# Avionics868.net
KiCad netlist of a schematic drawn in EAGLE
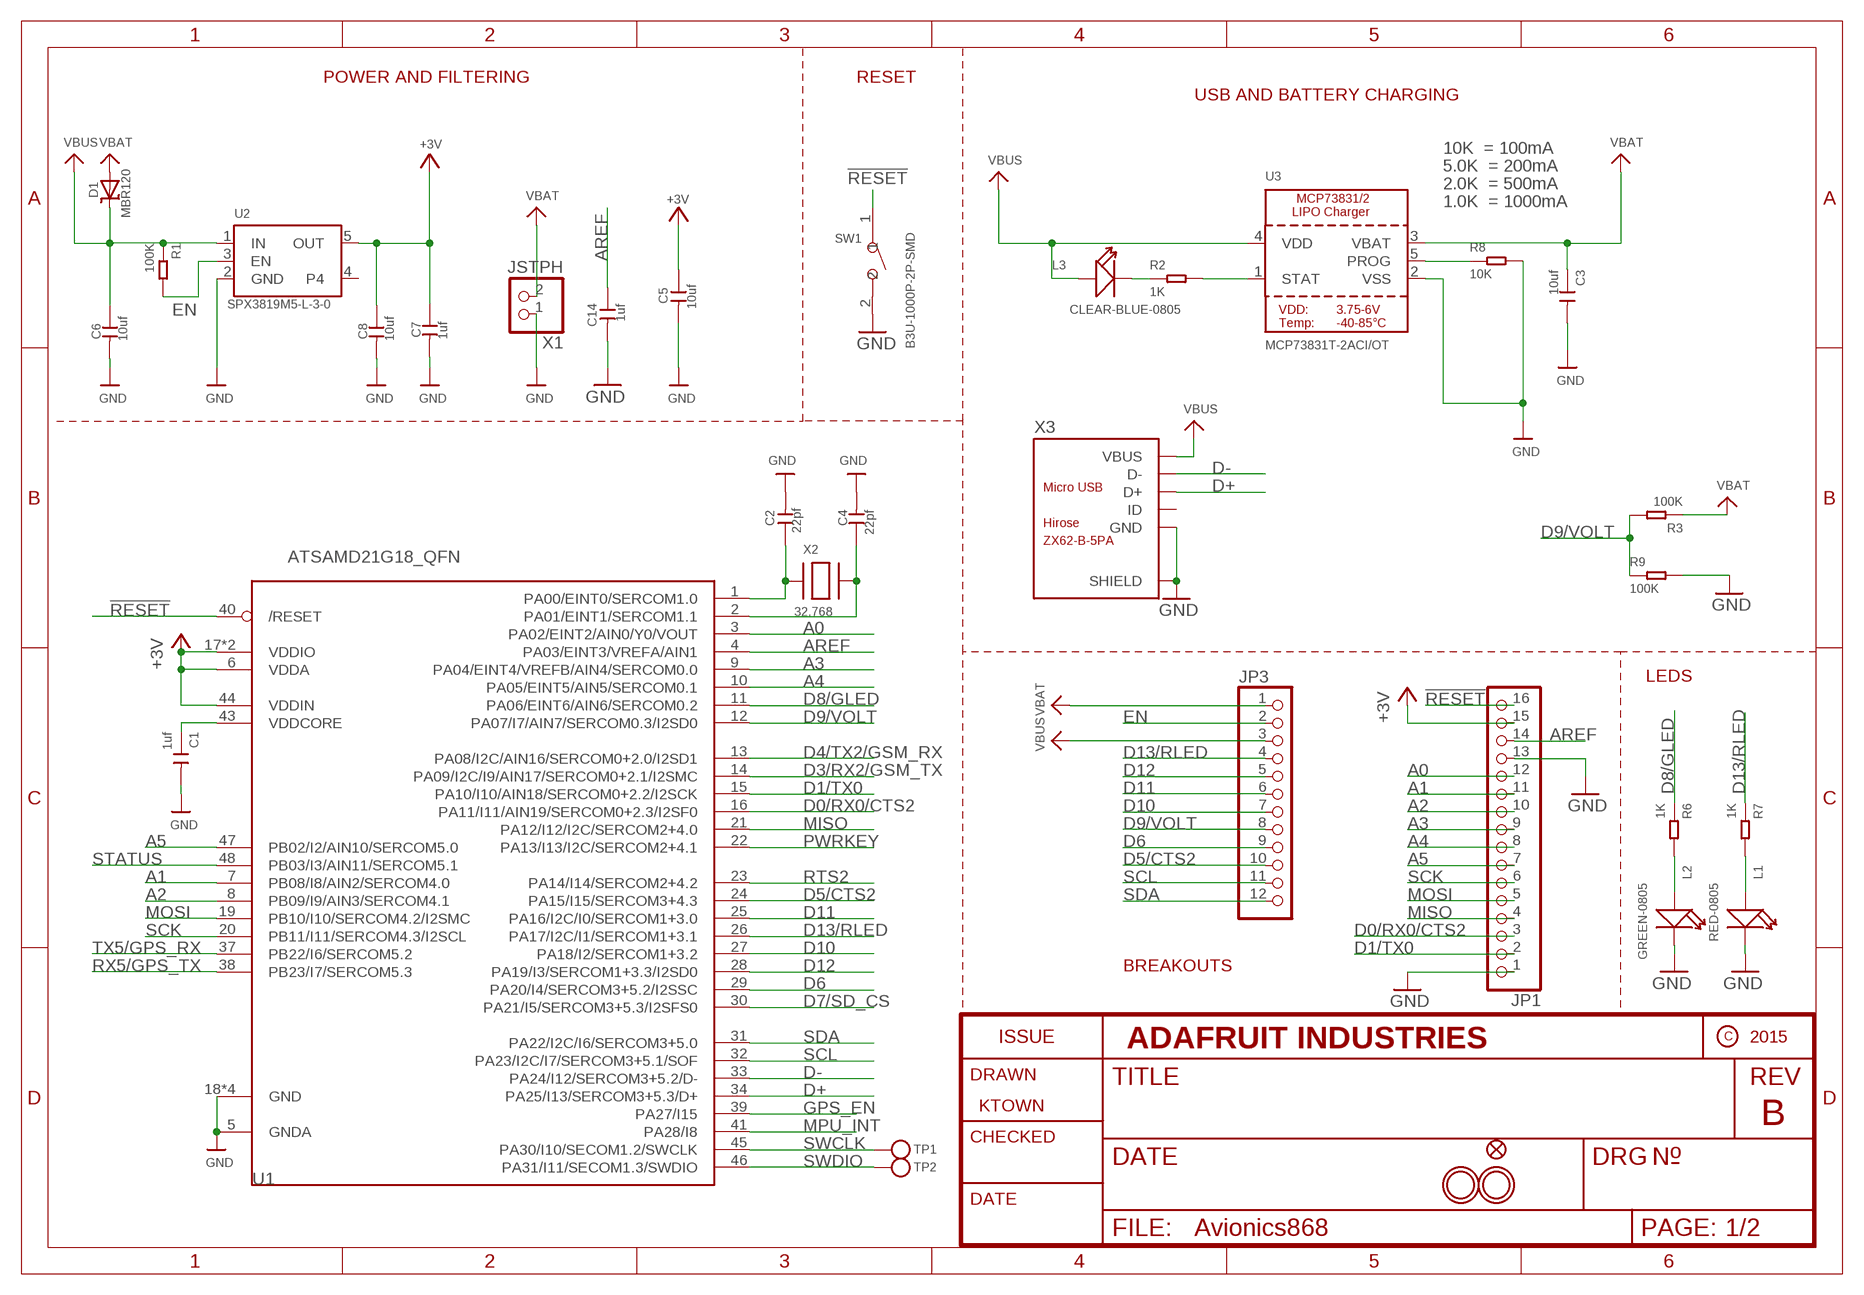
[diagram p0: schematic, sheet 1]
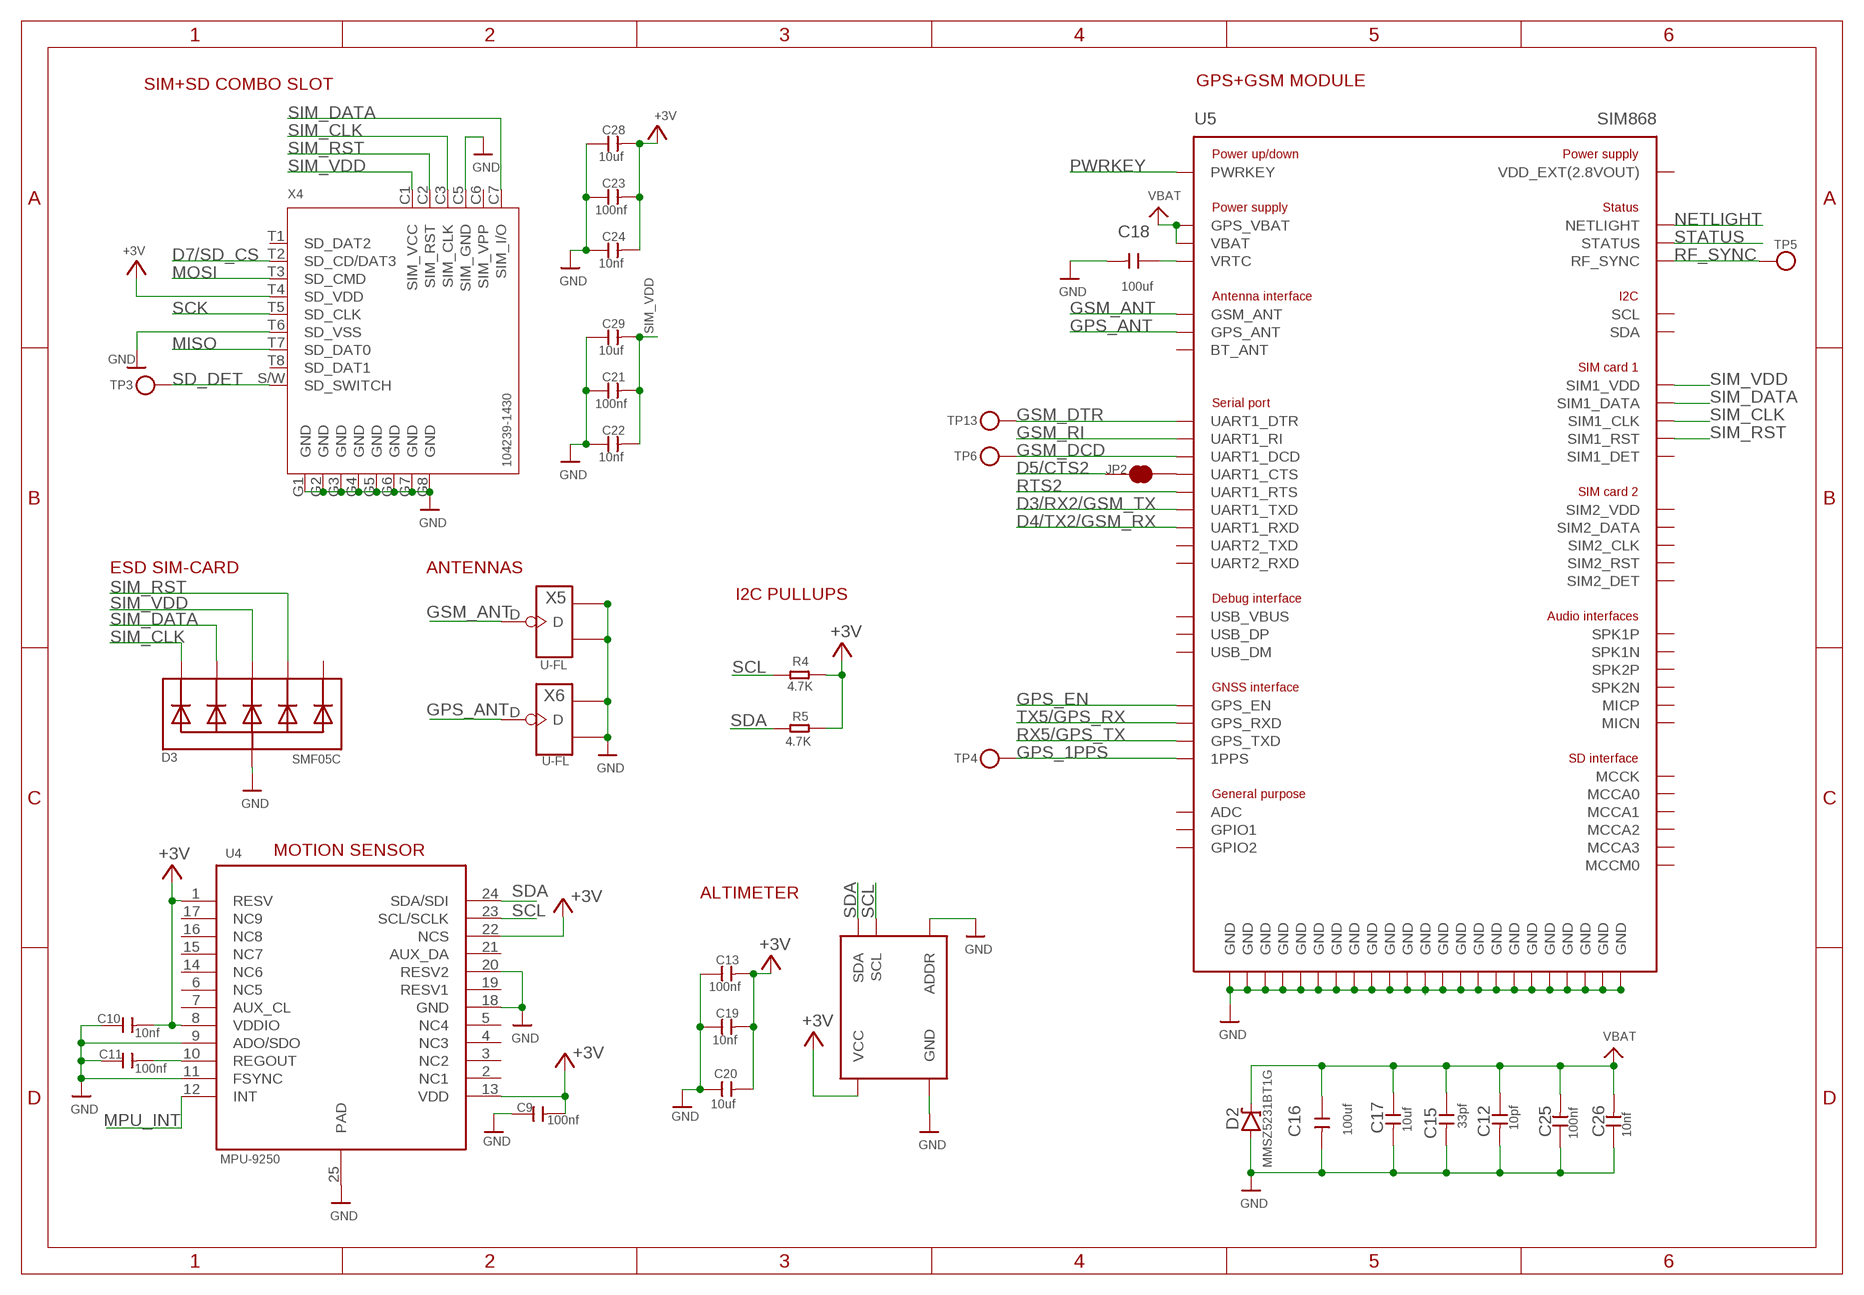
[diagram p1: schematic, sheet 2]

(export (version "E")
  (design (tool "Eeschema 10.0.6"))
  (components
    (comp (ref "C1")
      (value "1uf")
      (footprint "eagle-import:C0603")
      (fields (field (name "MPN") "CC0603KRX7R8BB105"))
      (libsource (lib "eagle-import") (part "CERAMIC-1UF-25V-10%-X7R(0603)"))
    )
    (comp (ref "C2")
      (value "22pf")
      (footprint "eagle-import:C0603")
      (fields (field (name "MPN") "CC0603JRNPO9BN220"))
      (libsource (lib "eagle-import") (part "CERAMIC-22PF-50V-5%-NPO(0603)"))
    )
    (comp (ref "C3")
      (value "10uf")
      (footprint "eagle-import:C0603")
      (fields (field (name "MPN") "CC0603KRX5R6BB106"))
      (libsource (lib "eagle-import") (part "CERAMIC-10UF-10V-10%-X5R(0603)"))
    )
    (comp (ref "C4")
      (value "22pf")
      (footprint "eagle-import:C0603")
      (fields (field (name "MPN") "CC0603JRNPO9BN220"))
      (libsource (lib "eagle-import") (part "CERAMIC-22PF-50V-5%-NPO(0603)"))
    )
    (comp (ref "C5")
      (value "10uf")
      (footprint "eagle-import:C0603")
      (fields (field (name "MPN") "CC0603KRX5R6BB106"))
      (libsource (lib "eagle-import") (part "CERAMIC-10UF-10V-10%-X5R(0603)"))
    )
    (comp (ref "C6")
      (value "10uf")
      (footprint "eagle-import:C0603")
      (fields (field (name "MPN") "CC0603KRX5R6BB106"))
      (libsource (lib "eagle-import") (part "CERAMIC-10UF-10V-10%-X5R(0603)"))
    )
    (comp (ref "C7")
      (value "1uf")
      (footprint "eagle-import:C0603")
      (fields (field (name "MPN") "CC0603KRX7R8BB105"))
      (libsource (lib "eagle-import") (part "CERAMIC-1UF-25V-10%-X7R(0603)"))
    )
    (comp (ref "C8")
      (value "10uf")
      (footprint "eagle-import:C0603")
      (fields (field (name "MPN") "CC0603KRX5R6BB106"))
      (libsource (lib "eagle-import") (part "CERAMIC-10UF-10V-10%-X5R(0603)"))
    )
    (comp (ref "C14")
      (value "1uf")
      (footprint "eagle-import:C0603")
      (fields (field (name "MPN") "CC0603KRX7R8BB105"))
      (libsource (lib "eagle-import") (part "CERAMIC-1UF-25V-10%-X7R(0603)"))
    )
    (comp (ref "D1")
      (value "MBR120")
      (footprint "eagle-import:SOD-123")
      (libsource (lib "eagle-import") (part "DIODE-SCHOTTKYSOD-123"))
    )
    (comp (ref "JP1")
      (value "HEADER-1X16ROUND")
      (footprint "eagle-import:1X16_ROUND")
      (libsource (lib "eagle-import") (part "HEADER-1X16ROUND"))
    )
    (comp (ref "JP3")
      (value "HEADER-1X12")
      (footprint "eagle-import:1X12_ROUND")
      (libsource (lib "eagle-import") (part "HEADER-1X12"))
    )
    (comp (ref "L1")
      (value "RED-0805")
      (footprint "eagle-import:LED-0805")
      (fields (field (name "MPN") "17-215SURC/S530-A2/TR8"))
      (libsource (lib "eagle-import") (part "SMD-LED-CLEAR-RED(0805)"))
    )
    (comp (ref "L2")
      (value "GREEN-0805")
      (footprint "eagle-import:LED-0805")
      (fields (field (name "MPN") "17-215SYGC/S530-E2/TR8"))
      (libsource (lib "eagle-import") (part "SMD-LED-CLEAR-GREEN(0805)"))
    )
    (comp (ref "L3")
      (value "CLEAR-BLUE-0805")
      (footprint "eagle-import:LED-0805")
      (fields (field (name "MPN") "EL-17-215/BHC-AN1P2/3T"))
      (libsource (lib "eagle-import") (part "SMD-LED-CLEAR-BLUE(0805)"))
    )
    (comp (ref "R1")
      (value "100K")
      (footprint "eagle-import:R0603")
      (fields (field (name "MPN") "RC0603JR-07100KL"))
      (libsource (lib "eagle-import") (part "SMD-RES-100K-5%-1/10W(0603)"))
    )
    (comp (ref "R2")
      (value "1K")
      (footprint "eagle-import:R0603")
      (fields (field (name "MPN") "RC0603JR-071KL"))
      (libsource (lib "eagle-import") (part "SMD-RES-1K-5%-1/10W(0603)"))
    )
    (comp (ref "R3")
      (value "100K")
      (footprint "eagle-import:R0603")
      (fields (field (name "MPN") "RC0603FR-07100KL"))
      (libsource (lib "eagle-import") (part "SMD-RES-100K-1%-1/10W(0603)"))
    )
    (comp (ref "R6")
      (value "1K")
      (footprint "eagle-import:R0603")
      (fields (field (name "MPN") "RC0603JR-071KL"))
      (libsource (lib "eagle-import") (part "SMD-RES-1K-5%-1/10W(0603)"))
    )
    (comp (ref "R7")
      (value "1K")
      (footprint "eagle-import:R0603")
      (fields (field (name "MPN") "RC0603JR-071KL"))
      (libsource (lib "eagle-import") (part "SMD-RES-1K-5%-1/10W(0603)"))
    )
    (comp (ref "R8")
      (value "10K")
      (footprint "eagle-import:R0603")
      (fields (field (name "MPN") "RC0603JR-0710KL"))
      (libsource (lib "eagle-import") (part "SMD-RES-10K-5%-1/10W(0603)"))
    )
    (comp (ref "R9")
      (value "100K")
      (footprint "eagle-import:R0603")
      (fields (field (name "MPN") "RC0603FR-07100KL"))
      (libsource (lib "eagle-import") (part "SMD-RES-100K-1%-1/10W(0603)"))
    )
    (comp (ref "SW1")
      (value "B3U-1000P-2P-SMD")
      (footprint "eagle-import:SW2-2.6-3.0X2.5X1.2+0.4MM")
      (libsource (lib "eagle-import") (part "SMD-BUTTON(2P-3.0X2.5X1.2+0.4MM)-B3U-1000P-2P-SMD"))
    )
    (comp (ref "TP1")
      (value "TESTPOINTROUND1.5MM")
      (footprint "eagle-import:TESTPOINT_ROUND_1.5MM")
      (libsource (lib "eagle-import") (part "TESTPOINTROUND1.5MM"))
    )
    (comp (ref "TP2")
      (value "TESTPOINTROUND1.5MM")
      (footprint "eagle-import:TESTPOINT_ROUND_1.5MM")
      (libsource (lib "eagle-import") (part "TESTPOINTROUND1.5MM"))
    )
    (comp (ref "U$31")
      (value "MOUNTINGHOLE2.5")
      (footprint "eagle-import:MOUNTINGHOLE_2.5_PLATED")
      (libsource (lib "eagle-import") (part "MOUNTINGHOLE2.5"))
    )
    (comp (ref "U$32")
      (value "MOUNTINGHOLE2.5")
      (footprint "eagle-import:MOUNTINGHOLE_2.5_PLATED")
      (libsource (lib "eagle-import") (part "MOUNTINGHOLE2.5"))
    )
    (comp (ref "U$34")
      (value "FIDUCIAL\"\"")
      (footprint "eagle-import:FIDUCIAL_1MM")
      (libsource (lib "eagle-import") (part "FIDUCIAL{dblquote}{dblquote}"))
    )
    (comp (ref "U1")
      (value "ATSAMD21G18_QFN")
      (footprint "eagle-import:TQFN48_7MM")
      (libsource (lib "eagle-import") (part "ATSAMD21J_QFN"))
    )
    (comp (ref "U2")
      (value "SPX3819M5-L-3-0")
      (footprint "eagle-import:SOT23-5")
      (libsource (lib "eagle-import") (part "VREG_SOT23-5"))
    )
    (comp (ref "U3")
      (value "MCP73831T-2ACI/OT")
      (footprint "eagle-import:SOT23-5")
      (libsource (lib "eagle-import") (part "MCP73831/2"))
    )
    (comp (ref "X1")
      (value "JSTPH")
      (footprint "eagle-import:JSTPH2")
      (libsource (lib "eagle-import") (part "CON_JST_PH_2PIN"))
    )
    (comp (ref "X2")
      (value "32.768")
      (footprint "eagle-import:XTAL3215")
      (libsource (lib "eagle-import") (part "XTAL-3.2X1.5"))
    )
    (comp (ref "X3")
      (value "ZX62-B-5PA")
      (footprint "eagle-import:MICRO-USB5+6P-SMD-0.65-AB")
      (fields (field (name "MFR") "Generic") (field (name "MPN") "AO1SB141B1-067"))
      (libsource (lib "eagle-import") (part "AO1SB141B1-067"))
    )
    (comp (ref "C9")
      (value "100nf")
      (footprint "eagle-import:C0603")
      (fields (field (name "MPN") "CC0603KRX7R9BB104"))
      (libsource (lib "eagle-import") (part "CERAMIC-100NF-50V-10%-X7R(0603)"))
    )
    (comp (ref "C10")
      (value "10nf")
      (footprint "eagle-import:C0603")
      (fields (field (name "MPN") "CC0603KRX7R9BB103"))
      (libsource (lib "eagle-import") (part "CERAMIC-10NF-50V-10%-X7R(0603)"))
    )
    (comp (ref "C11")
      (value "100nf")
      (footprint "eagle-import:C0603")
      (fields (field (name "MPN") "CC0603KRX7R9BB104"))
      (libsource (lib "eagle-import") (part "CERAMIC-100NF-50V-10%-X7R(0603)"))
    )
    (comp (ref "C12")
      (value "10pf")
      (footprint "eagle-import:C0603")
      (fields (field (name "MPN") "CC0603JRNPO9BN100"))
      (libsource (lib "eagle-import") (part "CERAMIC-10PF-50V-5%-NPO(0603)"))
    )
    (comp (ref "C13")
      (value "100nf")
      (footprint "eagle-import:C0603")
      (fields (field (name "MPN") "CC0603KRX7R9BB104"))
      (libsource (lib "eagle-import") (part "CERAMIC-100NF-50V-10%-X7R(0603)"))
    )
    (comp (ref "C15")
      (value "33pf")
      (footprint "eagle-import:C0603")
      (fields (field (name "MPN") "CC0603JRNPO9BN330"))
      (libsource (lib "eagle-import") (part "CERAMIC-33PF-50V-5%-NPO(0603)"))
    )
    (comp (ref "C16")
      (value "100uf")
      (footprint "eagle-import:C1206")
      (fields (field (name "MPN") "GRM31CR60J107ME39L"))
      (libsource (lib "eagle-import") (part "CERAMIC-100UF-6.3V-20%-X5R(1206)"))
    )
    (comp (ref "C17")
      (value "10uf")
      (footprint "eagle-import:C0603")
      (fields (field (name "MPN") "CC0603KRX5R6BB106"))
      (libsource (lib "eagle-import") (part "CERAMIC-10UF-10V-10%-X5R(0603)"))
    )
    (comp (ref "C18")
      (value "100uf")
      (footprint "eagle-import:C1206")
      (fields (field (name "MPN") "GRM31CR60J107ME39L"))
      (libsource (lib "eagle-import") (part "CERAMIC-100UF-6.3V-20%-X5R(1206)"))
    )
    (comp (ref "C19")
      (value "10nf")
      (footprint "eagle-import:C0603")
      (fields (field (name "MPN") "CC0603KRX7R9BB103"))
      (libsource (lib "eagle-import") (part "CERAMIC-10NF-50V-10%-X7R(0603)"))
    )
    (comp (ref "C20")
      (value "10uf")
      (footprint "eagle-import:C0603")
      (fields (field (name "MPN") "CC0603KRX5R6BB106"))
      (libsource (lib "eagle-import") (part "CERAMIC-10UF-10V-10%-X5R(0603)"))
    )
    (comp (ref "C21")
      (value "100nf")
      (footprint "eagle-import:C0603")
      (fields (field (name "MPN") "CC0603KRX7R9BB104"))
      (libsource (lib "eagle-import") (part "CERAMIC-100NF-50V-10%-X7R(0603)"))
    )
    (comp (ref "C22")
      (value "10nf")
      (footprint "eagle-import:C0603")
      (fields (field (name "MPN") "CC0603KRX7R9BB103"))
      (libsource (lib "eagle-import") (part "CERAMIC-10NF-50V-10%-X7R(0603)"))
    )
    (comp (ref "C23")
      (value "100nf")
      (footprint "eagle-import:C0603")
      (fields (field (name "MPN") "CC0603KRX7R9BB104"))
      (libsource (lib "eagle-import") (part "CERAMIC-100NF-50V-10%-X7R(0603)"))
    )
    (comp (ref "C24")
      (value "10nf")
      (footprint "eagle-import:C0603")
      (fields (field (name "MPN") "CC0603KRX7R9BB103"))
      (libsource (lib "eagle-import") (part "CERAMIC-10NF-50V-10%-X7R(0603)"))
    )
    (comp (ref "C25")
      (value "100nf")
      (footprint "eagle-import:C0603")
      (fields (field (name "MPN") "CC0603KRX7R9BB104"))
      (libsource (lib "eagle-import") (part "CERAMIC-100NF-50V-10%-X7R(0603)"))
    )
    (comp (ref "C26")
      (value "10nf")
      (footprint "eagle-import:C0603")
      (fields (field (name "MPN") "CC0603KRX7R9BB103"))
      (libsource (lib "eagle-import") (part "CERAMIC-10NF-50V-10%-X7R(0603)"))
    )
    (comp (ref "C28")
      (value "10uf")
      (footprint "eagle-import:C0603")
      (fields (field (name "MPN") "CC0603KRX5R6BB106"))
      (libsource (lib "eagle-import") (part "CERAMIC-10UF-10V-10%-X5R(0603)"))
    )
    (comp (ref "C29")
      (value "10uf")
      (footprint "eagle-import:C0603")
      (fields (field (name "MPN") "CC0603KRX5R6BB106"))
      (libsource (lib "eagle-import") (part "CERAMIC-10UF-10V-10%-X5R(0603)"))
    )
    (comp (ref "D2")
      (value "MMSZ5231BT1G")
      (footprint "eagle-import:SOD-123")
      (fields (field (name "MFR") "ON SEMICONDUCTOR"))
      (libsource (lib "eagle-import") (part "MMSZ5231BT1G"))
    )
    (comp (ref "D3")
      (value "SMF05C")
      (footprint "eagle-import:SOT363")
      (libsource (lib "eagle-import") (part "TVSARRAY_5LANE"))
    )
    (comp (ref "JP2")
      (value "JUMPER-PAD-2-NC_BY_TRACE")
      (footprint "eagle-import:PAD-JUMPER-2-NC_BY_TRACE_YES_SILK")
      (libsource (lib "eagle-import") (part "JUMPER-PAD-2-NC_BY_TRACE"))
    )
    (comp (ref "R4")
      (value "4.7K")
      (footprint "eagle-import:R0603")
      (fields (field (name "MPN") "RC0603JR-074K7L"))
      (libsource (lib "eagle-import") (part "SMD-RES-4.7K-5%-1/10W(0603)"))
    )
    (comp (ref "R5")
      (value "4.7K")
      (footprint "eagle-import:R0603")
      (fields (field (name "MPN") "RC0603JR-074K7L"))
      (libsource (lib "eagle-import") (part "SMD-RES-4.7K-5%-1/10W(0603)"))
    )
    (comp (ref "TP3")
      (value "TESTPOINTROUND1.5MM")
      (footprint "eagle-import:TESTPOINT_ROUND_1.5MM")
      (libsource (lib "eagle-import") (part "TESTPOINTROUND1.5MM"))
    )
    (comp (ref "TP4")
      (value "TESTPOINTROUND1.5MM")
      (footprint "eagle-import:TESTPOINT_ROUND_1.5MM")
      (libsource (lib "eagle-import") (part "TESTPOINTROUND1.5MM"))
    )
    (comp (ref "TP5")
      (value "TESTPOINTROUND1.5MM")
      (footprint "eagle-import:TESTPOINT_ROUND_1.5MM")
      (libsource (lib "eagle-import") (part "TESTPOINTROUND1.5MM"))
    )
    (comp (ref "TP6")
      (value "TESTPOINTROUND1.5MM")
      (footprint "eagle-import:TESTPOINT_ROUND_1.5MM")
      (libsource (lib "eagle-import") (part "TESTPOINTROUND1.5MM"))
    )
    (comp (ref "TP13")
      (value "TESTPOINTROUND1.5MM")
      (footprint "eagle-import:TESTPOINT_ROUND_1.5MM")
      (libsource (lib "eagle-import") (part "TESTPOINTROUND1.5MM"))
    )
    (comp (ref "U4")
      (value "MPU-9250")
      (footprint "eagle-import:LEAD-QFN24")
      (libsource (lib "eagle-import") (part "MPU-9250"))
    )
    (comp (ref "U5")
      (value "SIM868")
      (footprint "eagle-import:SIM868")
      (libsource (lib "eagle-import") (part "SIM868"))
    )
    (comp (ref "U6")
      (value "BMP280")
      (footprint "eagle-import:LGA-8")
      (libsource (lib "eagle-import") (part "BMP280"))
    )
    (comp (ref "X4")
      (value "104239-1430")
      (footprint "eagle-import:MOLEX-SD+SIM-104239")
      (fields (field (name "MPN") "VSHO-21-3301"))
      (libsource (lib "eagle-import") (part "MOLEX-SD+SIM-104239"))
    )
    (comp (ref "X5")
      (value "U-FL")
      (footprint "eagle-import:U-FL3P-SMD-2.6X2.6X1.0MM")
      (libsource (lib "eagle-import") (part "ANTENNA-CONN-U-FL(3P)"))
    )
    (comp (ref "X6")
      (value "U-FL")
      (footprint "eagle-import:U-FL3P-SMD-2.6X2.6X1.0MM")
      (libsource (lib "eagle-import") (part "ANTENNA-CONN-U-FL(3P)"))
    )
  )
  (nets
    (net (code "1") (name "+3V") (class "Default")
      (node (ref "C10") (pin "2") (pinfunction "2_2") (pintype "passive"))
      (node (ref "C13") (pin "2") (pinfunction "2_2") (pintype "passive"))
      (node (ref "C19") (pin "2") (pinfunction "2_2") (pintype "passive"))
      (node (ref "C20") (pin "2") (pinfunction "2_2") (pintype "passive"))
      (node (ref "C23") (pin "2") (pinfunction "2_2") (pintype "passive"))
      (node (ref "C24") (pin "2") (pinfunction "2_2") (pintype "passive"))
      (node (ref "C28") (pin "2") (pinfunction "2_2") (pintype "passive"))
      (node (ref "C5") (pin "1") (pinfunction "1_1") (pintype "passive"))
      (node (ref "C7") (pin "1") (pinfunction "1_1") (pintype "passive"))
      (node (ref "C8") (pin "1") (pinfunction "1_1") (pintype "passive"))
      (node (ref "C9") (pin "2") (pinfunction "2_2") (pintype "passive"))
      (node (ref "JP1") (pin "15") (pinfunction "15_15") (pintype "passive"))
      (node (ref "R4") (pin "2") (pinfunction "2_2") (pintype "passive"))
      (node (ref "R5") (pin "2") (pinfunction "2_2") (pintype "passive"))
      (node (ref "U1") (pin "17") (pinfunction "VDDIO_17") (pintype "power_in"))
      (node (ref "U1") (pin "36") (pinfunction "VDDIO_36") (pintype "power_in"))
      (node (ref "U1") (pin "44") (pinfunction "VDDIN_44") (pintype "power_in"))
      (node (ref "U1") (pin "6") (pinfunction "VDDA_6") (pintype "power_in"))
      (node (ref "U2") (pin "5") (pinfunction "OUT_5") (pintype "power_in"))
      (node (ref "U4") (pin "1") (pinfunction "RESV_1") (pintype "bidirectional"))
      (node (ref "U4") (pin "13") (pinfunction "VDD_13") (pintype "bidirectional"))
      (node (ref "U4") (pin "22") (pinfunction "NCS_22") (pintype "bidirectional"))
      (node (ref "U4") (pin "8") (pinfunction "VDDIO_8") (pintype "bidirectional"))
      (node (ref "U6") (pin "P2") (pinfunction "VCC_P2") (pintype "bidirectional"))
      (node (ref "U6") (pin "P6") (pinfunction "VCC_P6") (pintype "bidirectional"))
      (node (ref "U6") (pin "P8") (pinfunction "VCC_P8") (pintype "bidirectional"))
      (node (ref "X4") (pin "T4") (pinfunction "SD_VDD_T4") (pintype "bidirectional"))
    )
    (net (code "2") (name "A0") (class "Default")
      (node (ref "JP1") (pin "12") (pinfunction "12_12") (pintype "passive"))
      (node (ref "U1") (pin "3") (pinfunction "PA02/EINT2/AIN0/Y0/VOUT_3") (pintype "bidirectional"))
    )
    (net (code "3") (name "A1") (class "Default")
      (node (ref "JP1") (pin "11") (pinfunction "11_11") (pintype "passive"))
      (node (ref "U1") (pin "7") (pinfunction "PB08/I8/AIN2/SERCOM4.0_7") (pintype "bidirectional"))
    )
    (net (code "4") (name "A2") (class "Default")
      (node (ref "JP1") (pin "10") (pinfunction "10_10") (pintype "passive"))
      (node (ref "U1") (pin "8") (pinfunction "PB09/I9/AIN3/SERCOM4.1_8") (pintype "bidirectional"))
    )
    (net (code "5") (name "A3") (class "Default")
      (node (ref "JP1") (pin "9") (pinfunction "9_9") (pintype "passive"))
      (node (ref "U1") (pin "9") (pinfunction "PA04/EINT4/VREFB/AIN4/SERCOM0.0_9") (pintype "bidirectional"))
    )
    (net (code "6") (name "A4") (class "Default")
      (node (ref "JP1") (pin "8") (pinfunction "8_8") (pintype "passive"))
      (node (ref "U1") (pin "10") (pinfunction "PA05/EINT5/AIN5/SERCOM0.1_10") (pintype "bidirectional"))
    )
    (net (code "7") (name "A5") (class "Default")
      (node (ref "JP1") (pin "7") (pinfunction "7_7") (pintype "passive"))
      (node (ref "U1") (pin "47") (pinfunction "PB02/I2/AIN10/SERCOM5.0_47") (pintype "bidirectional"))
    )
    (net (code "8") (name "AREF") (class "Default")
      (node (ref "C14") (pin "1") (pinfunction "1_1") (pintype "passive"))
      (node (ref "JP1") (pin "14") (pinfunction "14_14") (pintype "passive"))
      (node (ref "U1") (pin "4") (pinfunction "PA03/EINT3/VREFA/AIN1_4") (pintype "bidirectional"))
    )
    (net (code "9") (name "D+") (class "Default")
      (node (ref "U1") (pin "34") (pinfunction "PA25/I13/SERCOM3+5.3/D+_34") (pintype "bidirectional"))
      (node (ref "X3") (pin "3") (pinfunction "D+_3") (pintype "bidirectional"))
    )
    (net (code "10") (name "D-") (class "Default")
      (node (ref "U1") (pin "33") (pinfunction "PA24/I12/SERCOM3+5.2/D-_33") (pintype "bidirectional"))
      (node (ref "X3") (pin "2") (pinfunction "D-_2") (pintype "bidirectional"))
    )
    (net (code "11") (name "D0{slash}RX0{slash}CTS2") (class "Default")
      (node (ref "JP1") (pin "3") (pinfunction "3_3") (pintype "passive"))
      (node (ref "U1") (pin "16") (pinfunction "PA11/I11/AIN19/SERCOM0+2.3/I2SF0_16") (pintype "bidirectional"))
    )
    (net (code "12") (name "D1{slash}TX0") (class "Default")
      (node (ref "JP1") (pin "2") (pinfunction "2_2") (pintype "passive"))
      (node (ref "U1") (pin "15") (pinfunction "PA10/I10/AIN18/SERCOM0+2.2/I2SCK_15") (pintype "bidirectional"))
    )
    (net (code "13") (name "D3{slash}RX2{slash}GSM_TX") (class "Default")
      (node (ref "U1") (pin "14") (pinfunction "PA09/I2C/I9/AIN17/SERCOM0+2.1/I2SMC_14") (pintype "bidirectional"))
      (node (ref "U5") (pin "1_") (pinfunction "UART1_TXD_1_") (pintype "output"))
    )
    (net (code "14") (name "D4{slash}TX2{slash}GSM_RX") (class "Default")
      (node (ref "U1") (pin "13") (pinfunction "PA08/I2C/AIN16/SERCOM0+2.0/I2SD1_13") (pintype "bidirectional"))
      (node (ref "U5") (pin "2_") (pinfunction "UART1_RXD_2_") (pintype "input"))
    )
    (net (code "15") (name "D5{slash}CTS2") (class "Default")
      (node (ref "JP2") (pin "1") (pinfunction "1_1") (pintype "passive"))
      (node (ref "JP3") (pin "10") (pinfunction "10_10") (pintype "passive"))
      (node (ref "U1") (pin "24") (pinfunction "PA15/I15/SERCOM3+4.3_24") (pintype "bidirectional"))
    )
    (net (code "16") (name "D6") (class "Default")
      (node (ref "JP3") (pin "9") (pinfunction "9_9") (pintype "passive"))
      (node (ref "U1") (pin "29") (pinfunction "PA20/I4/SERCOM3+5.2/I2SSC_29") (pintype "bidirectional"))
    )
    (net (code "17") (name "D7{slash}SD_CS") (class "Default")
      (node (ref "U1") (pin "30") (pinfunction "PA21/I5/SERCOM3+5.3/I2SFS0_30") (pintype "bidirectional"))
      (node (ref "X4") (pin "T2") (pinfunction "SD_CD/DAT3_T2") (pintype "bidirectional"))
    )
    (net (code "18") (name "D8{slash}GLED") (class "Default")
      (node (ref "R6") (pin "1") (pinfunction "1_1") (pintype "passive"))
      (node (ref "U1") (pin "11") (pinfunction "PA06/EINT6/AIN6/SERCOM0.2_11") (pintype "bidirectional"))
    )
    (net (code "19") (name "D9{slash}VOLT") (class "Default")
      (node (ref "JP3") (pin "8") (pinfunction "8_8") (pintype "passive"))
      (node (ref "R3") (pin "2") (pinfunction "2_2") (pintype "passive"))
      (node (ref "R9") (pin "1") (pinfunction "1_1") (pintype "passive"))
      (node (ref "U1") (pin "12") (pinfunction "PA07/I7/AIN7/SERCOM0.3/I2SD0_12") (pintype "bidirectional"))
    )
    (net (code "20") (name "D10") (class "Default")
      (node (ref "JP3") (pin "7") (pinfunction "7_7") (pintype "passive"))
      (node (ref "U1") (pin "27") (pinfunction "PA18/I2/SERCOM1+3.2_27") (pintype "bidirectional"))
    )
    (net (code "21") (name "D11") (class "Default")
      (node (ref "JP3") (pin "6") (pinfunction "6_6") (pintype "passive"))
      (node (ref "U1") (pin "25") (pinfunction "PA16/I2C/I0/SERCOM1+3.0_25") (pintype "bidirectional"))
    )
    (net (code "22") (name "D12") (class "Default")
      (node (ref "JP3") (pin "5") (pinfunction "5_5") (pintype "passive"))
      (node (ref "U1") (pin "28") (pinfunction "PA19/I3/SERCOM1+3.3/I2SD0_28") (pintype "bidirectional"))
    )
    (net (code "23") (name "D13{slash}RLED") (class "Default")
      (node (ref "JP3") (pin "4") (pinfunction "4_4") (pintype "passive"))
      (node (ref "R7") (pin "1") (pinfunction "1_1") (pintype "passive"))
      (node (ref "U1") (pin "26") (pinfunction "PA17/I2C/I1/SERCOM1+3.1_26") (pintype "bidirectional"))
    )
    (net (code "24") (name "EN") (class "Default")
      (node (ref "JP3") (pin "2") (pinfunction "2_2") (pintype "passive"))
      (node (ref "R1") (pin "2") (pinfunction "2_2") (pintype "passive"))
      (node (ref "U2") (pin "3") (pinfunction "EN_3") (pintype "input"))
    )
    (net (code "25") (name "GND") (class "Default")
      (node (ref "C1") (pin "2") (pinfunction "2_2") (pintype "passive"))
      (node (ref "C10") (pin "1") (pinfunction "1_1") (pintype "passive"))
      (node (ref "C11") (pin "1") (pinfunction "1_1") (pintype "passive"))
      (node (ref "C12") (pin "2") (pinfunction "2_2") (pintype "passive"))
      (node (ref "C13") (pin "1") (pinfunction "1_1") (pintype "passive"))
      (node (ref "C14") (pin "2") (pinfunction "2_2") (pintype "passive"))
      (node (ref "C15") (pin "2") (pinfunction "2_2") (pintype "passive"))
      (node (ref "C16") (pin "2") (pinfunction "2_2") (pintype "passive"))
      (node (ref "C17") (pin "2") (pinfunction "2_2") (pintype "passive"))
      (node (ref "C18") (pin "2") (pinfunction "2_2") (pintype "passive"))
      (node (ref "C19") (pin "1") (pinfunction "1_1") (pintype "passive"))
      (node (ref "C2") (pin "2") (pinfunction "2_2") (pintype "passive"))
      (node (ref "C20") (pin "1") (pinfunction "1_1") (pintype "passive"))
      (node (ref "C21") (pin "1") (pinfunction "1_1") (pintype "passive"))
      (node (ref "C22") (pin "1") (pinfunction "1_1") (pintype "passive"))
      (node (ref "C23") (pin "1") (pinfunction "1_1") (pintype "passive"))
      (node (ref "C24") (pin "1") (pinfunction "1_1") (pintype "passive"))
      (node (ref "C25") (pin "1") (pinfunction "1_1") (pintype "passive"))
      (node (ref "C26") (pin "1") (pinfunction "1_1") (pintype "passive"))
      (node (ref "C28") (pin "1") (pinfunction "1_1") (pintype "passive"))
      (node (ref "C29") (pin "1") (pinfunction "1_1") (pintype "passive"))
      (node (ref "C3") (pin "2") (pinfunction "2_2") (pintype "passive"))
      (node (ref "C4") (pin "2") (pinfunction "2_2") (pintype "passive"))
      (node (ref "C5") (pin "2") (pinfunction "2_2") (pintype "passive"))
      (node (ref "C6") (pin "2") (pinfunction "2_2") (pintype "passive"))
      (node (ref "C7") (pin "2") (pinfunction "2_2") (pintype "passive"))
      (node (ref "C8") (pin "2") (pinfunction "2_2") (pintype "passive"))
      (node (ref "C9") (pin "1") (pinfunction "1_1") (pintype "passive"))
      (node (ref "D2") (pin "A") (pinfunction "A_A") (pintype "passive"))
      (node (ref "D3") (pin "2") (pinfunction "A_2") (pintype "passive"))
      (node (ref "JP1") (pin "1") (pinfunction "1_1") (pintype "passive"))
      (node (ref "JP1") (pin "13") (pinfunction "13_13") (pintype "passive"))
      (node (ref "L1") (pin "-") (pinfunction "-_-") (pintype "passive"))
      (node (ref "L2") (pin "-") (pinfunction "-_-") (pintype "passive"))
      (node (ref "R8") (pin "2") (pinfunction "2_2") (pintype "passive"))
      (node (ref "R9") (pin "2") (pinfunction "2_2") (pintype "passive"))
      (node (ref "SW1") (pin "2") (pinfunction "2_2") (pintype "bidirectional"))
      (node (ref "U1") (pin "18") (pinfunction "GND_18") (pintype "power_in"))
      (node (ref "U1") (pin "35") (pinfunction "GND_35") (pintype "power_in"))
      (node (ref "U1") (pin "42") (pinfunction "GND_42") (pintype "power_in"))
      (node (ref "U1") (pin "5") (pinfunction "GNDA_5") (pintype "power_in"))
      (node (ref "U1") (pin "THERMAL") (pinfunction "GND_THERMAL") (pintype "power_in"))
      (node (ref "U2") (pin "2") (pinfunction "GND_2") (pintype "power_in"))
      (node (ref "U3") (pin "2") (pinfunction "VSS_2") (pintype "power_in"))
      (node (ref "U4") (pin "11") (pinfunction "FSYNC_11") (pintype "bidirectional"))
      (node (ref "U4") (pin "18") (pinfunction "GND_18") (pintype "bidirectional"))
      (node (ref "U4") (pin "20") (pinfunction "RESV2_20") (pintype "bidirectional"))
      (node (ref "U4") (pin "25") (pinfunction "PAD_25") (pintype "bidirectional"))
      (node (ref "U4") (pin "9") (pinfunction "ADO/SDO_9") (pintype "bidirectional"))
      (node (ref "U5") (pin "13_") (pinfunction "GND_13_") (pintype "power_in"))
      (node (ref "U5") (pin "19_") (pinfunction "GND_19_") (pintype "power_in"))
      (node (ref "U5") (pin "21_") (pinfunction "GND_21_") (pintype "power_in"))
      (node (ref "U5") (pin "27_") (pinfunction "GND_27_") (pintype "power_in"))
      (node (ref "U5") (pin "30_") (pinfunction "GND_30_") (pintype "power_in"))
      (node (ref "U5") (pin "31_") (pinfunction "GND_31_") (pintype "power_in"))
      (node (ref "U5") (pin "33_") (pinfunction "GND_33_") (pintype "power_in"))
      (node (ref "U5") (pin "36_") (pinfunction "GND_36_") (pintype "power_in"))
      (node (ref "U5") (pin "37_") (pinfunction "GND_37_") (pintype "power_in"))
      (node (ref "U5") (pin "45_") (pinfunction "GND_45_") (pintype "power_in"))
      (node (ref "U5") (pin "63_") (pinfunction "GND_63_") (pintype "power_in"))
      (node (ref "U5") (pin "66_") (pinfunction "GND_66_") (pintype "power_in"))
      (node (ref "U5") (pin "67_") (pinfunction "GND_67_") (pintype "power_in"))
      (node (ref "U5") (pin "69_") (pinfunction "GND_69_") (pintype "power_in"))
      (node (ref "U5") (pin "70_") (pinfunction "GND_70_") (pintype "power_in"))
      (node (ref "U5") (pin "71_") (pinfunction "GND_71_") (pintype "power_in"))
      (node (ref "U5") (pin "72_") (pinfunction "GND_72_") (pintype "power_in"))
      (node (ref "U5") (pin "73_") (pinfunction "GND_73_") (pintype "power_in"))
      (node (ref "U5") (pin "74_") (pinfunction "GND_74_") (pintype "power_in"))
      (node (ref "U5") (pin "75_") (pinfunction "GND_75_") (pintype "power_in"))
      (node (ref "U5") (pin "76_") (pinfunction "GND_76_") (pintype "power_in"))
      (node (ref "U5") (pin "77_") (pinfunction "GND_77_") (pintype "power_in"))
      (node (ref "U5") (pin "8_") (pinfunction "GND_8_") (pintype "power_in"))
      (node (ref "U6") (pin "P1") (pinfunction "GND_P1") (pintype "bidirectional"))
      (node (ref "U6") (pin "P5") (pinfunction "ADDR_P5") (pintype "bidirectional"))
      (node (ref "U6") (pin "P7") (pinfunction "GND_P7") (pintype "bidirectional"))
      (node (ref "X1") (pin "1") (pinfunction "1_1") (pintype "passive"))
      (node (ref "X3") (pin "5") (pinfunction "GND_5") (pintype "power_in"))
      (node (ref "X3") (pin "P1") (pinfunction "SHIELD_P1") (pintype "power_in"))
      (node (ref "X3") (pin "P2") (pinfunction "SHIELD_P2") (pintype "power_in"))
      (node (ref "X3") (pin "P3") (pinfunction "SHIELD_P3") (pintype "power_in"))
      (node (ref "X3") (pin "P4") (pinfunction "SHIELD_P4") (pintype "power_in"))
      (node (ref "X3") (pin "P5") (pinfunction "SHIELD_P5") (pintype "power_in"))
      (node (ref "X3") (pin "P6") (pinfunction "SHIELD_P6") (pintype "power_in"))
      (node (ref "X4") (pin "C5") (pinfunction "SIM_GND_C5") (pintype "bidirectional"))
      (node (ref "X4") (pin "G1") (pinfunction "GND_G1") (pintype "power_in"))
      (node (ref "X4") (pin "G2") (pinfunction "GND_G2") (pintype "power_in"))
      (node (ref "X4") (pin "G3") (pinfunction "GND_G3") (pintype "power_in"))
      (node (ref "X4") (pin "G4") (pinfunction "GND_G4") (pintype "power_in"))
      (node (ref "X4") (pin "G5") (pinfunction "GND_G5") (pintype "power_in"))
      (node (ref "X4") (pin "G6") (pinfunction "GND_G6") (pintype "power_in"))
      (node (ref "X4") (pin "G7") (pinfunction "GND_G7") (pintype "power_in"))
      (node (ref "X4") (pin "G8") (pinfunction "GND_G8") (pintype "power_in"))
      (node (ref "X4") (pin "T6") (pinfunction "SD_VSS_T6") (pintype "bidirectional"))
      (node (ref "X5") (pin "GND1") (pinfunction "GND1_GND1") (pintype "bidirectional"))
      (node (ref "X5") (pin "GND2") (pinfunction "GND2_GND2") (pintype "bidirectional"))
      (node (ref "X6") (pin "GND1") (pinfunction "GND1_GND1") (pintype "bidirectional"))
      (node (ref "X6") (pin "GND2") (pinfunction "GND2_GND2") (pintype "bidirectional"))
    )
    (net (code "26") (name "GPS_1PPS") (class "Default")
      (node (ref "TP4") (pin "P$1") (pinfunction "P$1_P$1") (pintype "bidirectional"))
      (node (ref "U5") (pin "60_") (pinfunction "1PPS_60_") (pintype "input"))
    )
    (net (code "27") (name "GPS_ANT") (class "Default")
      (node (ref "U5") (pin "68_") (pinfunction "GPS_ANT_68_") (pintype "bidirectional"))
      (node (ref "X6") (pin "D") (pinfunction "D_D") (pintype "bidirectional"))
    )
    (net (code "28") (name "GPS_EN") (class "Default")
      (node (ref "U1") (pin "39") (pinfunction "PA27/I15_39") (pintype "bidirectional"))
      (node (ref "U5") (pin "59_") (pinfunction "GPS_EN_59_") (pintype "input"))
    )
    (net (code "29") (name "GSM_ANT") (class "Default")
      (node (ref "U5") (pin "32_") (pinfunction "GSM_ANT_32_") (pintype "input"))
      (node (ref "X5") (pin "D") (pinfunction "D_D") (pintype "bidirectional"))
    )
    (net (code "30") (name "GSM_DCD") (class "Default")
      (node (ref "TP6") (pin "P$1") (pinfunction "P$1_P$1") (pintype "bidirectional"))
      (node (ref "U5") (pin "5_") (pinfunction "UART1_DCD_5_") (pintype "output"))
    )
    (net (code "31") (name "GSM_DTR") (class "Default")
      (node (ref "TP13") (pin "P$1") (pinfunction "P$1_P$1") (pintype "bidirectional"))
      (node (ref "U5") (pin "6_") (pinfunction "UART1_DTR_6_") (pintype "input"))
    )
    (net (code "32") (name "GSM_RI") (class "Default")
      (node (ref "U5") (pin "7_") (pinfunction "UART1_RI_7_") (pintype "output"))
    )
    (net (code "33") (name "MISO") (class "Default")
      (node (ref "JP1") (pin "4") (pinfunction "4_4") (pintype "passive"))
      (node (ref "U1") (pin "21") (pinfunction "PA12/I12/I2C/SERCOM2+4.0_21") (pintype "bidirectional"))
      (node (ref "X4") (pin "T7") (pinfunction "SD_DAT0_T7") (pintype "bidirectional"))
    )
    (net (code "34") (name "MOSI") (class "Default")
      (node (ref "JP1") (pin "5") (pinfunction "5_5") (pintype "passive"))
      (node (ref "U1") (pin "19") (pinfunction "PB10/I10/SERCOM4.2/I2SMC_19") (pintype "bidirectional"))
      (node (ref "X4") (pin "T3") (pinfunction "SD_CMD_T3") (pintype "bidirectional"))
    )
    (net (code "35") (name "MPU_INT") (class "Default")
      (node (ref "U1") (pin "41") (pinfunction "PA28/I8_41") (pintype "bidirectional"))
      (node (ref "U4") (pin "12") (pinfunction "INT_12") (pintype "bidirectional"))
    )
    (net (code "36") (name "NETLIGHT") (class "Default")
      (node (ref "U5") (pin "41_") (pinfunction "NETLIGHT_41_") (pintype "output"))
    )
    (net (code "37") (name "Net-(L1-Pad+)") (class "Default")
      (node (ref "L1") (pin "+") (pinfunction "+_+") (pintype "passive"))
      (node (ref "R7") (pin "2") (pinfunction "2_2") (pintype "passive"))
    )
    (net (code "38") (name "Net-(L2-Pad+)") (class "Default")
      (node (ref "L2") (pin "+") (pinfunction "+_+") (pintype "passive"))
      (node (ref "R6") (pin "2") (pinfunction "2_2") (pintype "passive"))
    )
    (net (code "39") (name "Net-(L3-Pad-)") (class "Default")
      (node (ref "L3") (pin "-") (pinfunction "-_-") (pintype "passive"))
      (node (ref "R2") (pin "1") (pinfunction "1_1") (pintype "passive"))
    )
    (net (code "40") (name "Net-(U1-PA00{slash}EINT0{slash}SERCOM1.0)") (class "Default")
      (node (ref "C2") (pin "1") (pinfunction "1_1") (pintype "passive"))
      (node (ref "U1") (pin "1") (pinfunction "PA00/EINT0/SERCOM1.0_1") (pintype "bidirectional"))
      (node (ref "X2") (pin "P$1") (pinfunction "P$1_P$1") (pintype "bidirectional"))
    )
    (net (code "41") (name "Net-(U1-PA01{slash}EINT1{slash}SERCOM1.1)") (class "Default")
      (node (ref "C4") (pin "1") (pinfunction "1_1") (pintype "passive"))
      (node (ref "U1") (pin "2") (pinfunction "PA01/EINT1/SERCOM1.1_2") (pintype "bidirectional"))
      (node (ref "X2") (pin "P$2") (pinfunction "P$2_P$2") (pintype "bidirectional"))
    )
    (net (code "42") (name "Net-(U1-VDDCORE)") (class "Default")
      (node (ref "C1") (pin "1") (pinfunction "1_1") (pintype "passive"))
      (node (ref "U1") (pin "43") (pinfunction "VDDCORE_43") (pintype "power_in"))
    )
    (net (code "43") (name "Net-(U3-PROG)") (class "Default")
      (node (ref "R8") (pin "1") (pinfunction "1_1") (pintype "passive"))
      (node (ref "U3") (pin "5") (pinfunction "PROG_5") (pintype "input"))
    )
    (net (code "44") (name "Net-(U3-STAT)") (class "Default")
      (node (ref "R2") (pin "2") (pinfunction "2_2") (pintype "passive"))
      (node (ref "U3") (pin "1") (pinfunction "STAT_1") (pintype "output"))
    )
    (net (code "45") (name "Net-(U4-REGOUT)") (class "Default")
      (node (ref "C11") (pin "2") (pinfunction "2_2") (pintype "passive"))
      (node (ref "U4") (pin "10") (pinfunction "REGOUT_10") (pintype "bidirectional"))
    )
    (net (code "46") (name "Net-(U5-UART1_CTS)") (class "Default")
      (node (ref "JP2") (pin "2") (pinfunction "2_2") (pintype "passive"))
      (node (ref "U5") (pin "4_") (pinfunction "UART1_CTS_4_") (pintype "output"))
    )
    (net (code "47") (name "Net-(U5-VRTC)") (class "Default")
      (node (ref "C18") (pin "1") (pinfunction "1_1") (pintype "passive"))
      (node (ref "U5") (pin "28_") (pinfunction "VRTC_28_") (pintype "power_in"))
    )
    (net (code "48") (name "PWRKEY") (class "Default")
      (node (ref "U1") (pin "22") (pinfunction "PA13/I13/I2C/SERCOM2+4.1_22") (pintype "bidirectional"))
      (node (ref "U5") (pin "39_") (pinfunction "PWRKEY_39_") (pintype "input"))
    )
    (net (code "49") (name "RF_SYNC") (class "Default")
      (node (ref "TP5") (pin "P$1") (pinfunction "P$1_P$1") (pintype "bidirectional"))
      (node (ref "U5") (pin "29_") (pinfunction "RF_SYNC_29_") (pintype "output"))
    )
    (net (code "50") (name "RTS2") (class "Default")
      (node (ref "U1") (pin "23") (pinfunction "PA14/I14/SERCOM2+4.2_23") (pintype "bidirectional"))
      (node (ref "U5") (pin "3_") (pinfunction "UART1_RTS_3_") (pintype "input"))
    )
    (net (code "51") (name "RX5{slash}GPS_TX") (class "Default")
      (node (ref "U1") (pin "38") (pinfunction "PB23/I7/SERCOM5.3_38") (pintype "bidirectional"))
      (node (ref "U5") (pin "61_") (pinfunction "GPS_TXD_61_") (pintype "output"))
    )
    (net (code "52") (name "SCK") (class "Default")
      (node (ref "JP1") (pin "6") (pinfunction "6_6") (pintype "passive"))
      (node (ref "U1") (pin "20") (pinfunction "PB11/I11/SERCOM4.3/I2SCL_20") (pintype "bidirectional"))
      (node (ref "X4") (pin "T5") (pinfunction "SD_CLK_T5") (pintype "bidirectional"))
    )
    (net (code "53") (name "SCL") (class "Default")
      (node (ref "JP3") (pin "11") (pinfunction "11_11") (pintype "passive"))
      (node (ref "R4") (pin "1") (pinfunction "1_1") (pintype "passive"))
      (node (ref "U1") (pin "32") (pinfunction "PA23/I2C/I7/SERCOM3+5.1/SOF_32") (pintype "bidirectional"))
      (node (ref "U4") (pin "23") (pinfunction "SCL/SCLK_23") (pintype "bidirectional"))
      (node (ref "U6") (pin "P4") (pinfunction "SCL_P4") (pintype "bidirectional"))
    )
    (net (code "54") (name "SDA") (class "Default")
      (node (ref "JP3") (pin "12") (pinfunction "12_12") (pintype "passive"))
      (node (ref "R5") (pin "1") (pinfunction "1_1") (pintype "passive"))
      (node (ref "U1") (pin "31") (pinfunction "PA22/I2C/I6/SERCOM3+5.0_31") (pintype "bidirectional"))
      (node (ref "U4") (pin "24") (pinfunction "SDA/SDI_24") (pintype "bidirectional"))
      (node (ref "U6") (pin "P3") (pinfunction "SDA_P3") (pintype "bidirectional"))
    )
    (net (code "55") (name "SD_DET") (class "Default")
      (node (ref "TP3") (pin "P$1") (pinfunction "P$1_P$1") (pintype "bidirectional"))
      (node (ref "X4") (pin "S/W") (pinfunction "SD_SWITCH_S/W") (pintype "bidirectional"))
    )
    (net (code "56") (name "SIM2_VDD") (class "Default")
      (node (ref "U5") (pin "56_") (pinfunction "SIM2_VDD_56_") (pintype "power_in"))
    )
    (net (code "57") (name "SIM_CLK") (class "Default")
      (node (ref "D3") (pin "1") (pinfunction "C1_1") (pintype "passive"))
      (node (ref "U5") (pin "16_") (pinfunction "SIM1_CLK_16_") (pintype "output"))
      (node (ref "X4") (pin "C3") (pinfunction "SIM_CLK_C3") (pintype "bidirectional"))
    )
    (net (code "58") (name "SIM_DATA") (class "Default")
      (node (ref "D3") (pin "3") (pinfunction "C2_3") (pintype "passive"))
      (node (ref "U5") (pin "15_") (pinfunction "SIM1_DATA_15_") (pintype "bidirectional"))
      (node (ref "X4") (pin "C7") (pinfunction "SIM_I/O_C7") (pintype "bidirectional"))
    )
    (net (code "59") (name "SIM_RST") (class "Default")
      (node (ref "D3") (pin "5") (pinfunction "C4_5") (pintype "passive"))
      (node (ref "U5") (pin "17_") (pinfunction "SIM1_RST_17_") (pintype "output"))
      (node (ref "X4") (pin "C2") (pinfunction "SIM_RST_C2") (pintype "bidirectional"))
    )
    (net (code "60") (name "SIM_VDD") (class "Default")
      (node (ref "C21") (pin "2") (pinfunction "2_2") (pintype "passive"))
      (node (ref "C22") (pin "2") (pinfunction "2_2") (pintype "passive"))
      (node (ref "C29") (pin "2") (pinfunction "2_2") (pintype "passive"))
      (node (ref "D3") (pin "4") (pinfunction "C3_4") (pintype "passive"))
      (node (ref "U5") (pin "18_") (pinfunction "SIM1_VDD_18_") (pintype "power_in"))
      (node (ref "X4") (pin "C1") (pinfunction "SIM_VCC_C1") (pintype "bidirectional"))
    )
    (net (code "61") (name "STATUS") (class "Default")
      (node (ref "U1") (pin "48") (pinfunction "PB03/I3/AIN11/SERCOM5.1_48") (pintype "bidirectional"))
      (node (ref "U5") (pin "42_") (pinfunction "STATUS_42_") (pintype "output"))
    )
    (net (code "62") (name "SWCLK") (class "Default")
      (node (ref "TP1") (pin "P$1") (pinfunction "P$1_P$1") (pintype "bidirectional"))
      (node (ref "U1") (pin "45") (pinfunction "PA30/I10/SECOM1.2/SWCLK_45") (pintype "bidirectional"))
    )
    (net (code "63") (name "SWDIO") (class "Default")
      (node (ref "TP2") (pin "P$1") (pinfunction "P$1_P$1") (pintype "bidirectional"))
      (node (ref "U1") (pin "46") (pinfunction "PA31/I11/SECOM1.3/SWDIO_46") (pintype "bidirectional"))
    )
    (net (code "64") (name "TX5{slash}GPS_RX") (class "Default")
      (node (ref "U1") (pin "37") (pinfunction "PB22/I6/SERCOM5.2_37") (pintype "bidirectional"))
      (node (ref "U5") (pin "62_") (pinfunction "GPS_RXD_62_") (pintype "input"))
    )
    (net (code "65") (name "USB_VBUS") (class "Default")
      (node (ref "U5") (pin "24_") (pinfunction "USB_VBUS_24_") (pintype "power_in"))
    )
    (net (code "66") (name "VBAT") (class "Default")
      (node (ref "C12") (pin "1") (pinfunction "1_1") (pintype "passive"))
      (node (ref "C15") (pin "1") (pinfunction "1_1") (pintype "passive"))
      (node (ref "C16") (pin "1") (pinfunction "1_1") (pintype "passive"))
      (node (ref "C17") (pin "1") (pinfunction "1_1") (pintype "passive"))
      (node (ref "C25") (pin "2") (pinfunction "2_2") (pintype "passive"))
      (node (ref "C26") (pin "2") (pinfunction "2_2") (pintype "passive"))
      (node (ref "C3") (pin "1") (pinfunction "1_1") (pintype "passive"))
      (node (ref "D1") (pin "A") (pinfunction "A_A") (pintype "passive"))
      (node (ref "D2") (pin "C") (pinfunction "C_C") (pintype "passive"))
      (node (ref "JP3") (pin "1") (pinfunction "1_1") (pintype "passive"))
      (node (ref "R3") (pin "1") (pinfunction "1_1") (pintype "passive"))
      (node (ref "U3") (pin "3") (pinfunction "VBAT_3") (pintype "power_in"))
      (node (ref "U5") (pin "34_") (pinfunction "GPS_VBAT_34_") (pintype "power_in"))
      (node (ref "U5") (pin "35_") (pinfunction "VBAT_35_") (pintype "power_in"))
      (node (ref "X1") (pin "2") (pinfunction "2_2") (pintype "passive"))
    )
    (net (code "67") (name "VBUS") (class "Default")
      (node (ref "C6") (pin "1") (pinfunction "1_1") (pintype "passive"))
      (node (ref "D1") (pin "C") (pinfunction "C_C") (pintype "passive"))
      (node (ref "JP3") (pin "3") (pinfunction "3_3") (pintype "passive"))
      (node (ref "L3") (pin "+") (pinfunction "+_+") (pintype "passive"))
      (node (ref "R1") (pin "1") (pinfunction "1_1") (pintype "passive"))
      (node (ref "U2") (pin "1") (pinfunction "IN_1") (pintype "power_in"))
      (node (ref "U3") (pin "4") (pinfunction "VDD_4") (pintype "power_in"))
      (node (ref "X3") (pin "1") (pinfunction "VBUS_1") (pintype "power_in"))
    )
    (net (code "68") (name "VDD_EXT(2.8VOUT)") (class "Default")
      (node (ref "U5") (pin "40_") (pinfunction "VDD_EXT(2.8VOUT)_40_") (pintype "power_in"))
    )
    (net (code "69") (name "unconnected-(D3-C5-Pad6)") (class "Default")
      (node (ref "D3") (pin "6") (pinfunction "C5_6") (pintype "passive"))
    )
    (net (code "70") (name "unconnected-(U2-P4-Pad4)") (class "Default")
      (node (ref "U2") (pin "4") (pinfunction "P4_4") (pintype "bidirectional"))
    )
    (net (code "71") (name "unconnected-(U4-AUX_CL-Pad7)") (class "Default")
      (node (ref "U4") (pin "7") (pinfunction "AUX_CL_7") (pintype "bidirectional"))
    )
    (net (code "72") (name "unconnected-(U4-AUX_DA-Pad21)") (class "Default")
      (node (ref "U4") (pin "21") (pinfunction "AUX_DA_21") (pintype "bidirectional"))
    )
    (net (code "73") (name "unconnected-(U4-NC1-Pad2)") (class "Default")
      (node (ref "U4") (pin "2") (pinfunction "NC1_2") (pintype "bidirectional"))
    )
    (net (code "74") (name "unconnected-(U4-NC2-Pad3)") (class "Default")
      (node (ref "U4") (pin "3") (pinfunction "NC2_3") (pintype "bidirectional"))
    )
    (net (code "75") (name "unconnected-(U4-NC3-Pad4)") (class "Default")
      (node (ref "U4") (pin "4") (pinfunction "NC3_4") (pintype "bidirectional"))
    )
    (net (code "76") (name "unconnected-(U4-NC4-Pad5)") (class "Default")
      (node (ref "U4") (pin "5") (pinfunction "NC4_5") (pintype "bidirectional"))
    )
    (net (code "77") (name "unconnected-(U4-NC5-Pad6)") (class "Default")
      (node (ref "U4") (pin "6") (pinfunction "NC5_6") (pintype "bidirectional"))
    )
    (net (code "78") (name "unconnected-(U4-NC6-Pad14)") (class "Default")
      (node (ref "U4") (pin "14") (pinfunction "NC6_14") (pintype "bidirectional"))
    )
    (net (code "79") (name "unconnected-(U4-NC7-Pad15)") (class "Default")
      (node (ref "U4") (pin "15") (pinfunction "NC7_15") (pintype "bidirectional"))
    )
    (net (code "80") (name "unconnected-(U4-NC8-Pad16)") (class "Default")
      (node (ref "U4") (pin "16") (pinfunction "NC8_16") (pintype "bidirectional"))
    )
    (net (code "81") (name "unconnected-(U4-NC9-Pad17)") (class "Default")
      (node (ref "U4") (pin "17") (pinfunction "NC9_17") (pintype "bidirectional"))
    )
    (net (code "82") (name "unconnected-(U4-RESV1-Pad19)") (class "Default")
      (node (ref "U4") (pin "19") (pinfunction "RESV1_19") (pintype "bidirectional"))
    )
    (net (code "83") (name "unconnected-(U5-ADC-Pad38_)") (class "Default")
      (node (ref "U5") (pin "38_") (pinfunction "ADC_38_") (pintype "input"))
    )
    (net (code "84") (name "unconnected-(U5-BT_ANT-Pad20_)") (class "Default")
      (node (ref "U5") (pin "20_") (pinfunction "BT_ANT_20_") (pintype "bidirectional"))
    )
    (net (code "85") (name "unconnected-(U5-GPIO1-Pad57_)") (class "Default")
      (node (ref "U5") (pin "57_") (pinfunction "GPIO1_57_") (pintype "bidirectional"))
    )
    (net (code "86") (name "unconnected-(U5-GPIO2-Pad58_)") (class "Default")
      (node (ref "U5") (pin "58_") (pinfunction "GPIO2_58_") (pintype "bidirectional"))
    )
    (net (code "87") (name "unconnected-(U5-MCCA0-Pad49_)") (class "Default")
      (node (ref "U5") (pin "49_") (pinfunction "MCCA0_49_") (pintype "bidirectional"))
    )
    (net (code "88") (name "unconnected-(U5-MCCA1-Pad48_)") (class "Default")
      (node (ref "U5") (pin "48_") (pinfunction "MCCA1_48_") (pintype "bidirectional"))
    )
    (net (code "89") (name "unconnected-(U5-MCCA2-Pad47_)") (class "Default")
      (node (ref "U5") (pin "47_") (pinfunction "MCCA2_47_") (pintype "bidirectional"))
    )
    (net (code "90") (name "unconnected-(U5-MCCA3-Pad46_)") (class "Default")
      (node (ref "U5") (pin "46_") (pinfunction "MCCA3_46_") (pintype "bidirectional"))
    )
    (net (code "91") (name "unconnected-(U5-MCCK-Pad50_)") (class "Default")
      (node (ref "U5") (pin "50_") (pinfunction "MCCK_50_") (pintype "bidirectional"))
    )
    (net (code "92") (name "unconnected-(U5-MCCM0-Pad51_)") (class "Default")
      (node (ref "U5") (pin "51_") (pinfunction "MCCM0_51_") (pintype "bidirectional"))
    )
    (net (code "93") (name "unconnected-(U5-MICN-Pad10_)") (class "Default")
      (node (ref "U5") (pin "10_") (pinfunction "MICN_10_") (pintype "input"))
    )
    (net (code "94") (name "unconnected-(U5-MICP-Pad9_)") (class "Default")
      (node (ref "U5") (pin "9_") (pinfunction "MICP_9_") (pintype "input"))
    )
    (net (code "95") (name "unconnected-(U5-SCL-Pad65_)") (class "Default")
      (node (ref "U5") (pin "65_") (pinfunction "SCL_65_") (pintype "output"))
    )
    (net (code "96") (name "unconnected-(U5-SDA-Pad64_)") (class "Default")
      (node (ref "U5") (pin "64_") (pinfunction "SDA_64_") (pintype "bidirectional"))
    )
    (net (code "97") (name "unconnected-(U5-SIM1_DET-Pad14_)") (class "Default")
      (node (ref "U5") (pin "14_") (pinfunction "SIM1_DET_14_") (pintype "input"))
    )
    (net (code "98") (name "unconnected-(U5-SIM2_CLK-Pad54_)") (class "Default")
      (node (ref "U5") (pin "54_") (pinfunction "SIM2_CLK_54_") (pintype "output"))
    )
    (net (code "99") (name "unconnected-(U5-SIM2_DATA-Pad53_)") (class "Default")
      (node (ref "U5") (pin "53_") (pinfunction "SIM2_DATA_53_") (pintype "bidirectional"))
    )
    (net (code "100") (name "unconnected-(U5-SIM2_DET-Pad52_)") (class "Default")
      (node (ref "U5") (pin "52_") (pinfunction "SIM2_DET_52_") (pintype "input"))
    )
    (net (code "101") (name "unconnected-(U5-SIM2_RST-Pad55_)") (class "Default")
      (node (ref "U5") (pin "55_") (pinfunction "SIM2_RST_55_") (pintype "output"))
    )
    (net (code "102") (name "unconnected-(U5-SPK1N-Pad12_)") (class "Default")
      (node (ref "U5") (pin "12_") (pinfunction "SPK1N_12_") (pintype "output"))
    )
    (net (code "103") (name "unconnected-(U5-SPK1P-Pad11_)") (class "Default")
      (node (ref "U5") (pin "11_") (pinfunction "SPK1P_11_") (pintype "output"))
    )
    (net (code "104") (name "unconnected-(U5-SPK2N-Pad43_)") (class "Default")
      (node (ref "U5") (pin "43_") (pinfunction "SPK2N_43_") (pintype "output"))
    )
    (net (code "105") (name "unconnected-(U5-SPK2P-Pad44_)") (class "Default")
      (node (ref "U5") (pin "44_") (pinfunction "SPK2P_44_") (pintype "output"))
    )
    (net (code "106") (name "unconnected-(U5-UART2_RXD-Pad23_)") (class "Default")
      (node (ref "U5") (pin "23_") (pinfunction "UART2_RXD_23_") (pintype "input"))
    )
    (net (code "107") (name "unconnected-(U5-UART2_TXD-Pad22_)") (class "Default")
      (node (ref "U5") (pin "22_") (pinfunction "UART2_TXD_22_") (pintype "output"))
    )
    (net (code "108") (name "unconnected-(U5-USB_DM-Pad26_)") (class "Default")
      (node (ref "U5") (pin "26_") (pinfunction "USB_DM_26_") (pintype "bidirectional"))
    )
    (net (code "109") (name "unconnected-(U5-USB_DP-Pad25_)") (class "Default")
      (node (ref "U5") (pin "25_") (pinfunction "USB_DP_25_") (pintype "bidirectional"))
    )
    (net (code "110") (name "unconnected-(X3-ID-Pad4)") (class "Default")
      (node (ref "X3") (pin "4") (pinfunction "ID_4") (pintype "bidirectional"))
    )
    (net (code "111") (name "unconnected-(X4-SD_DAT1-PadT8)") (class "Default")
      (node (ref "X4") (pin "T8") (pinfunction "SD_DAT1_T8") (pintype "bidirectional"))
    )
    (net (code "112") (name "unconnected-(X4-SD_DAT2-PadT1)") (class "Default")
      (node (ref "X4") (pin "T1") (pinfunction "SD_DAT2_T1") (pintype "bidirectional"))
    )
    (net (code "113") (name "unconnected-(X4-SIM_VPP-PadC6)") (class "Default")
      (node (ref "X4") (pin "C6") (pinfunction "SIM_VPP_C6") (pintype "bidirectional"))
    )
    (net (code "114") (name "~{RESET}") (class "Default")
      (node (ref "JP1") (pin "16") (pinfunction "16_16") (pintype "passive"))
      (node (ref "SW1") (pin "1") (pinfunction "1_1") (pintype "bidirectional"))
      (node (ref "U1") (pin "40") (pinfunction "/RESET_40") (pintype "bidirectional"))
    )
  )
)
